# Logic.net
KiCad netlist of a schematic drawn in EAGLE
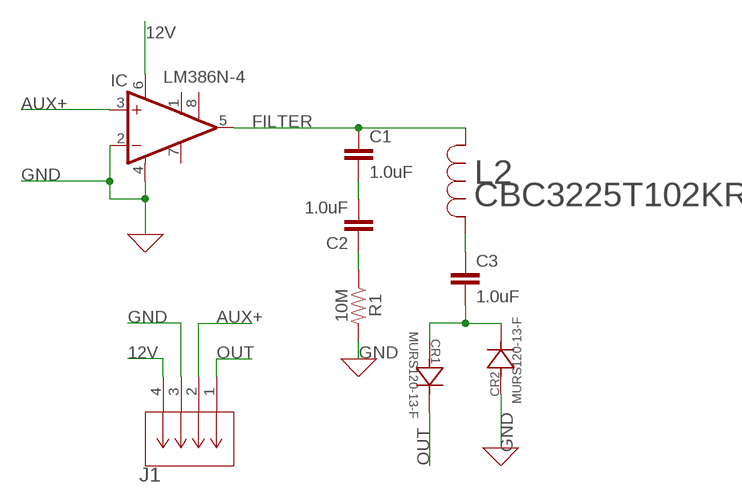
[diagram p0: schematic, sheet 1]

(export (version "E")
  (design (tool "Eeschema 10.0.6"))
  (components
    (comp (ref "C1")
      (value "1.0uF")
      (footprint "eagle-import:0603")
      (libsource (lib "eagle-import") (part "1.0UF-0603-16V-10%"))
    )
    (comp (ref "C2")
      (value "1.0uF")
      (footprint "eagle-import:0603")
      (libsource (lib "eagle-import") (part "1.0UF-0603-16V-10%"))
    )
    (comp (ref "C3")
      (value "1.0uF")
      (footprint "eagle-import:0603")
      (libsource (lib "eagle-import") (part "1.0UF-0603-16V-10%"))
    )
    (comp (ref "CR1")
      (value "MURS120-13-F")
      (footprint "eagle-import:SMB")
      (fields (field (name "MANUFACTURER_PART_NUMBER") "MURS12013F"))
      (libsource (lib "eagle-import") (part "MURS120-13-F"))
    )
    (comp (ref "CR2")
      (value "MURS120-13-F")
      (footprint "eagle-import:SMB")
      (fields (field (name "MANUFACTURER_PART_NUMBER") "MURS12013F"))
      (libsource (lib "eagle-import") (part "MURS120-13-F"))
    )
    (comp (ref "IC")
      (value "LM386N-4")
      (footprint "eagle-import:DIL08")
      (libsource (lib "eagle-import") (part "LM386?-N4"))
    )
    (comp (ref "J1")
      (value "SLW-104-01-T-S")
      (footprint "eagle-import:CON4_1X4_TU_SLW")
      (fields (field (name "MANUFACTURER_PART_NUMBER") "SLW10401TS"))
      (libsource (lib "eagle-import") (part "SLW-104-01-T-S"))
    )
    (comp (ref "L2")
      (value "CBC3225T102KR")
      (footprint "eagle-import:IND_CBC3225T100KRV")
      (libsource (lib "eagle-import") (part "CBC3225T102KR"))
    )
    (comp (ref "R1")
      (value "10M")
      (footprint "eagle-import:0603")
      (libsource (lib "eagle-import") (part "10MOHM-0603-1/10W-5%"))
    )
  )
  (nets
    (net (code "1") (name "/12V") (class "Default")
      (node (ref "IC") (pin "6") (pinfunction "VS_6") (pintype "power_in"))
      (node (ref "J1") (pin "4") (pinfunction "4_4") (pintype "passive"))
    )
    (net (code "2") (name "/AUX+") (class "Default")
      (node (ref "IC") (pin "3") (pinfunction "+IN_3") (pintype "input"))
      (node (ref "J1") (pin "2") (pinfunction "2_2") (pintype "passive"))
    )
    (net (code "3") (name "/FILTER") (class "Default")
      (node (ref "C1") (pin "1") (pinfunction "1_1") (pintype "passive"))
      (node (ref "IC") (pin "5") (pinfunction "OUT_5") (pintype "output"))
      (node (ref "L2") (pin "1") (pinfunction "1_1") (pintype "passive"))
    )
    (net (code "4") (name "/OUT") (class "Default")
      (node (ref "CR1") (pin "1") (pinfunction "1_1") (pintype "passive"))
      (node (ref "J1") (pin "1") (pinfunction "1_1") (pintype "passive"))
    )
    (net (code "5") (name "GND") (class "Default")
      (node (ref "CR2") (pin "2") (pinfunction "2_2") (pintype "passive"))
      (node (ref "IC") (pin "2") (pinfunction "-IN_2") (pintype "input"))
      (node (ref "IC") (pin "4") (pinfunction "GND_4") (pintype "power_in"))
      (node (ref "J1") (pin "3") (pinfunction "3_3") (pintype "passive"))
      (node (ref "R1") (pin "2") (pinfunction "2_2") (pintype "passive"))
    )
    (net (code "6") (name "Net-(C1-Pad2)") (class "Default")
      (node (ref "C1") (pin "2") (pinfunction "2_2") (pintype "passive"))
      (node (ref "C2") (pin "2") (pinfunction "2_2") (pintype "passive"))
    )
    (net (code "7") (name "Net-(C2-Pad1)") (class "Default")
      (node (ref "C2") (pin "1") (pinfunction "1_1") (pintype "passive"))
      (node (ref "R1") (pin "1") (pinfunction "1_1") (pintype "passive"))
    )
    (net (code "8") (name "Net-(C3-Pad1)") (class "Default")
      (node (ref "C3") (pin "1") (pinfunction "1_1") (pintype "passive"))
      (node (ref "L2") (pin "2") (pinfunction "2_2") (pintype "passive"))
    )
    (net (code "9") (name "Net-(C3-Pad2)") (class "Default")
      (node (ref "C3") (pin "2") (pinfunction "2_2") (pintype "passive"))
      (node (ref "CR1") (pin "2") (pinfunction "2_2") (pintype "passive"))
      (node (ref "CR2") (pin "1") (pinfunction "1_1") (pintype "passive"))
    )
    (net (code "10") (name "unconnected-(IC-BYPASS-Pad7)") (class "Default")
      (node (ref "IC") (pin "7") (pinfunction "BYPASS_7") (pintype "passive"))
    )
    (net (code "11") (name "unconnected-(IC-GAIN-Pad1)") (class "Default")
      (node (ref "IC") (pin "1") (pinfunction "GAIN_1") (pintype "passive"))
    )
    (net (code "12") (name "unconnected-(IC-GAIN-Pad8)") (class "Default")
      (node (ref "IC") (pin "8") (pinfunction "GAIN_8") (pintype "passive"))
    )
  )
)
